# DistribPower_PWR.net
KiCad netlist of a schematic drawn in Altium Designer
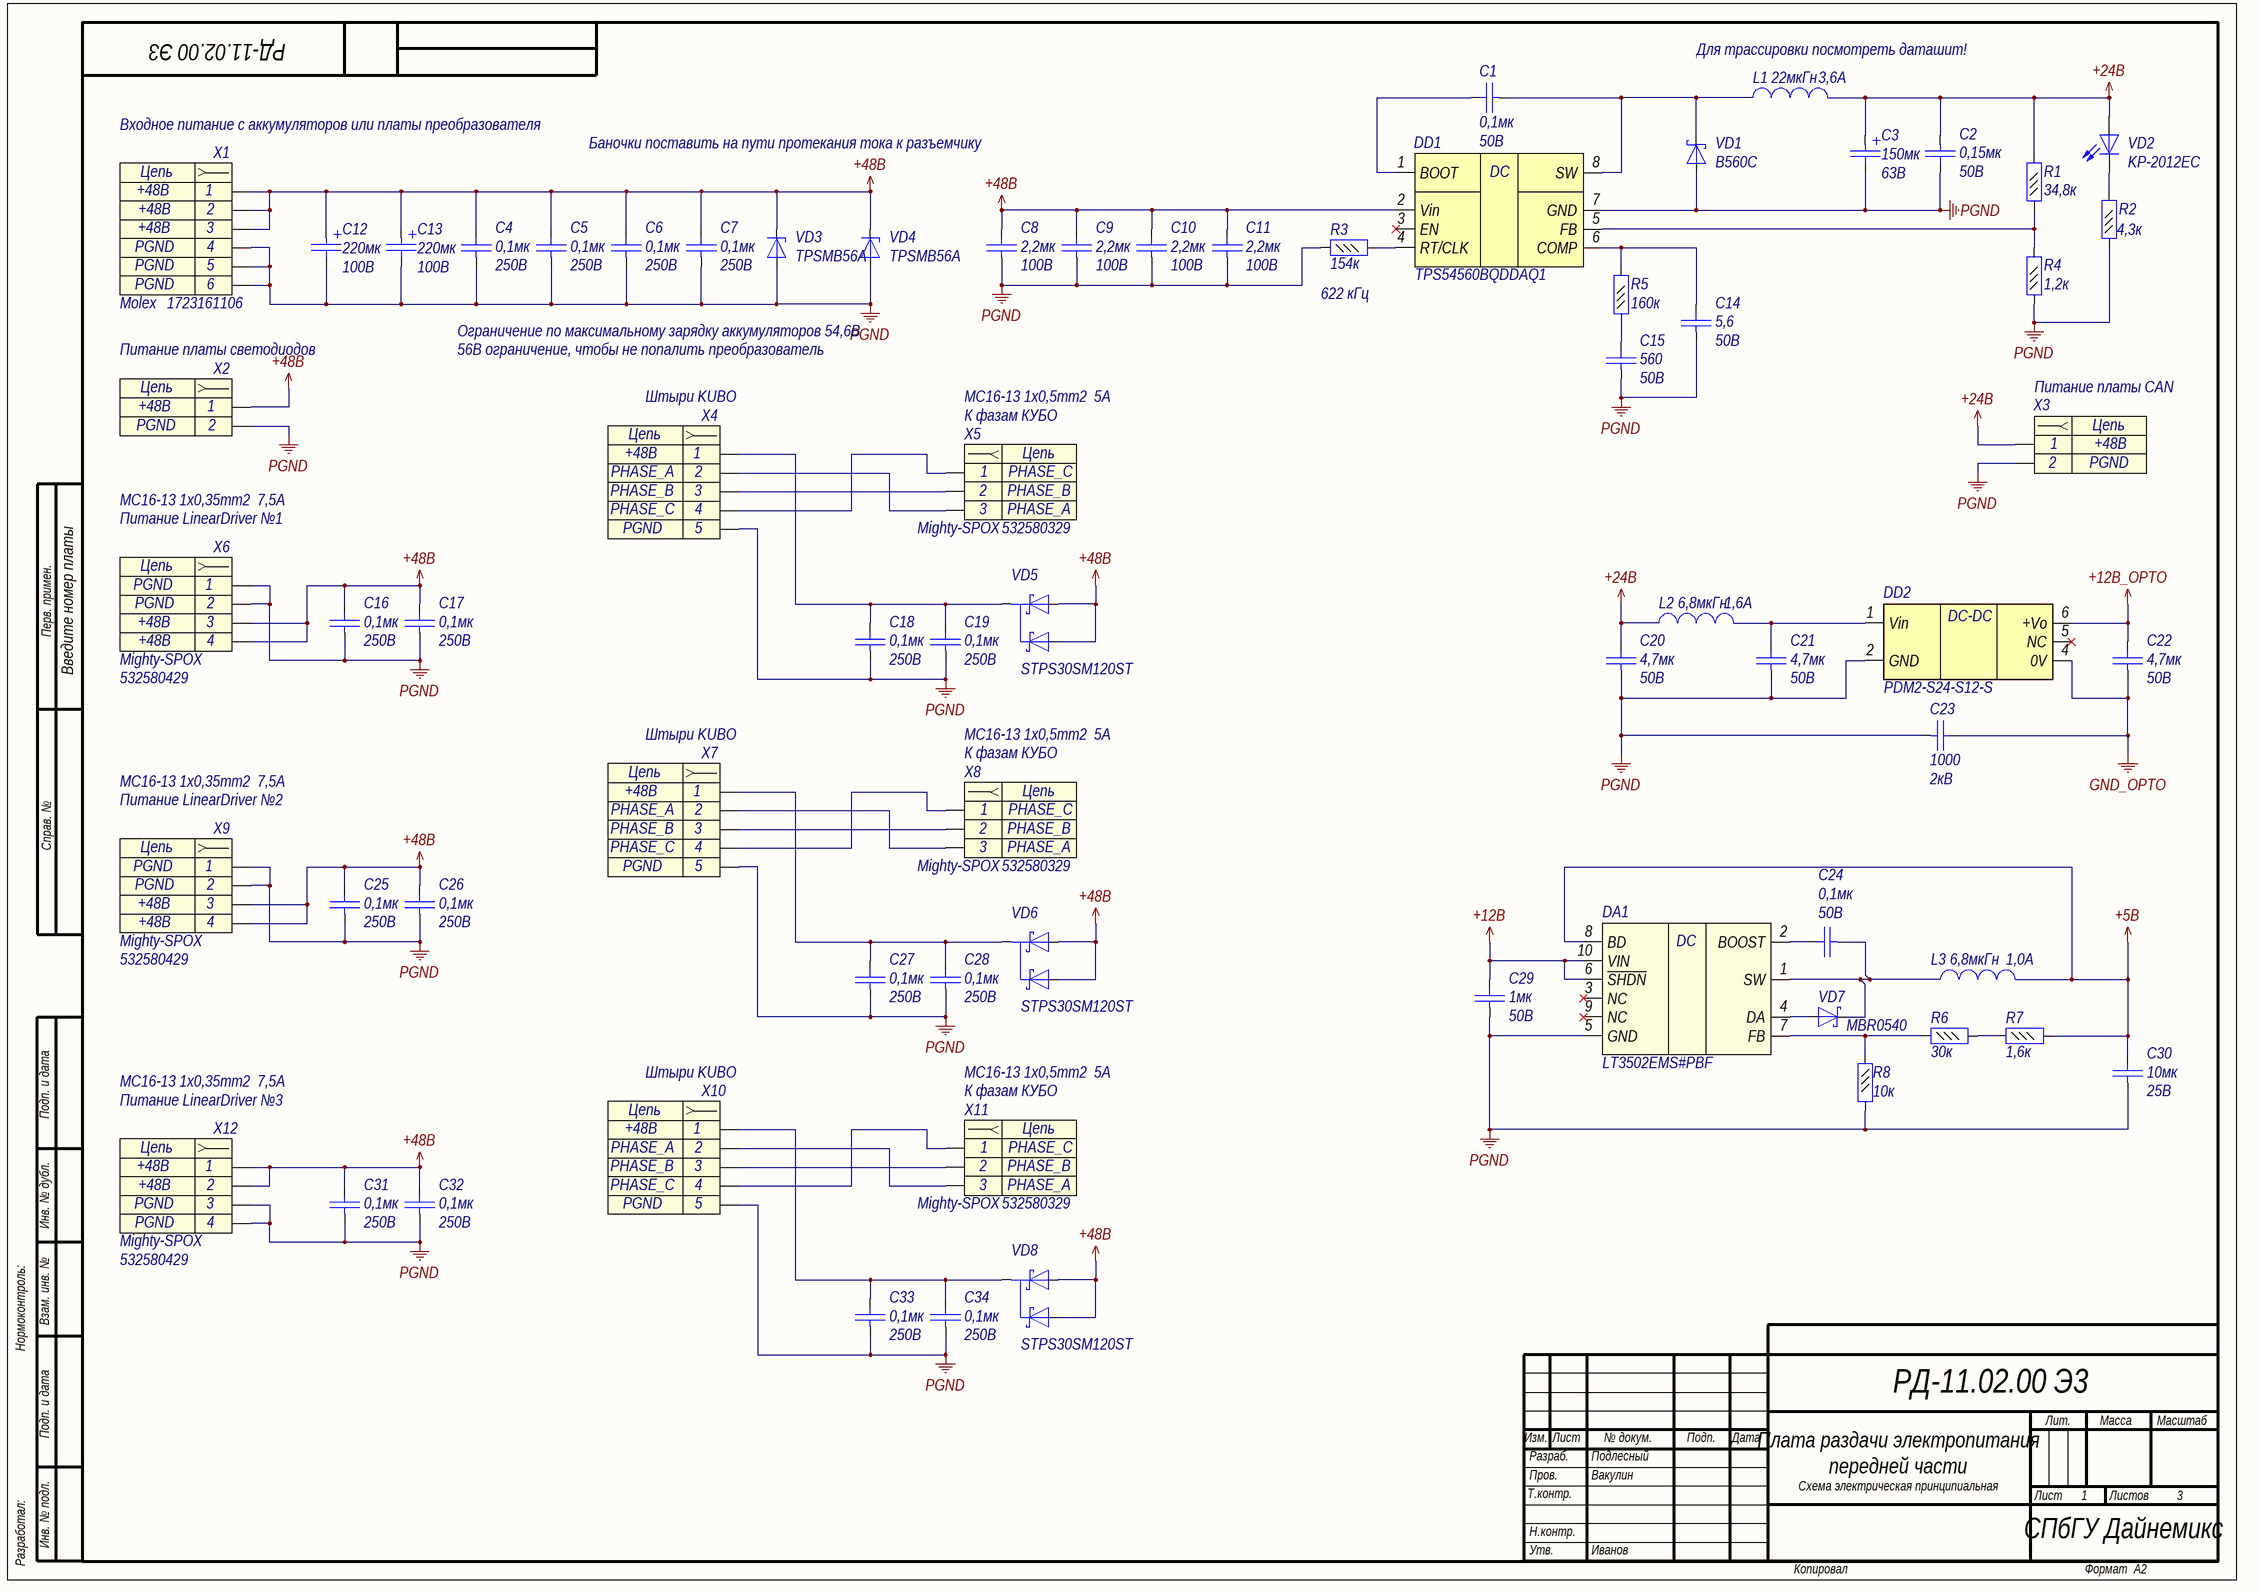
[diagram p0: DistribPower_PWR.SchDoc]

(export (version "E")
  (design (tool "Eeschema 10.0.6"))
  (components
    (comp (ref "C1")
      (value "0,1мк")
      (footprint "C0402")
      (description "Конденсатор")
      (fields (field (name "VOLTAGE") "50В") (field (name "PART NUMBER") "GRM155R71H104KE14D "))
      (libsource (lib "MOP44") (part "Capacitor"))
    )
    (comp (ref "C2")
      (value "0,15мк")
      (footprint "C1812")
      (description "Конденсатор")
      (fields (field (name "VOLTAGE") "50В") (field (name "PART NUMBER") "C4532C0G1H154J250KA "))
      (libsource (lib "MOP44") (part "Capacitor"))
    )
    (comp (ref "C3")
      (value "150мк")
      (footprint "Cap_SMD_radial_polar(10x16.5)")
      (description "Конденсатор полярный")
      (fields
        (field (name "VOLTAGE") "63B")
        (field (name "PART NUMBER") "EEH-ZS1J151P")
        (field (name "Comment") "Capacitor_pol")
      )
      (libsource (lib "MOP44") (part "Capacitor_pol"))
    )
    (comp (ref "C4")
      (value "0,1мк")
      (footprint "C1206")
      (description "Конденсатор")
      (fields
        (field (name "VOLTAGE") "250В")
        (field (name "PART NUMBER") "GRM31CR72E104K")
        (field (name "Comment") "Capacitor")
      )
      (libsource (lib "MOP44") (part "Capacitor"))
    )
    (comp (ref "C5")
      (value "0,1мк")
      (footprint "C1206")
      (description "Конденсатор")
      (fields
        (field (name "VOLTAGE") "250В")
        (field (name "PART NUMBER") "GRM31CR72E104K")
        (field (name "Comment") "Capacitor")
      )
      (libsource (lib "MOP44") (part "Capacitor"))
    )
    (comp (ref "C6")
      (value "0,1мк")
      (footprint "C1206")
      (description "Конденсатор")
      (fields
        (field (name "VOLTAGE") "250В")
        (field (name "PART NUMBER") "GRM31CR72E104K")
        (field (name "Comment") "Capacitor")
      )
      (libsource (lib "MOP44") (part "Capacitor"))
    )
    (comp (ref "C7")
      (value "0,1мк")
      (footprint "C1206")
      (description "Конденсатор")
      (fields
        (field (name "VOLTAGE") "250В")
        (field (name "PART NUMBER") "GRM31CR72E104K")
        (field (name "Comment") "Capacitor")
      )
      (libsource (lib "MOP44") (part "Capacitor"))
    )
    (comp (ref "C8")
      (value "2,2мк")
      (footprint "C1812")
      (description "Конденсатор")
      (fields (field (name "VOLTAGE") "100В") (field (name "PART NUMBER") "C4532X7R2A225M"))
      (libsource (lib "MOP44") (part "Capacitor"))
    )
    (comp (ref "C9")
      (value "2,2мк")
      (footprint "C1812")
      (description "Конденсатор")
      (fields (field (name "VOLTAGE") "100В") (field (name "PART NUMBER") "C4532X7R2A225M"))
      (libsource (lib "MOP44") (part "Capacitor"))
    )
    (comp (ref "C10")
      (value "2,2мк")
      (footprint "C1812")
      (description "Конденсатор")
      (fields (field (name "VOLTAGE") "100В") (field (name "PART NUMBER") "C4532X7R2A225M"))
      (libsource (lib "MOP44") (part "Capacitor"))
    )
    (comp (ref "C11")
      (value "2,2мк")
      (footprint "C1812")
      (description "Конденсатор")
      (fields (field (name "VOLTAGE") "100В") (field (name "PART NUMBER") "C4532X7R2A225M"))
      (libsource (lib "MOP44") (part "Capacitor"))
    )
    (comp (ref "C12")
      (value "220мк")
      (footprint "K50-35(12.5X25)_V")
      (description "Конденсатор полярный")
      (fields
        (field (name "VOLTAGE") "100B")
        (field (name "PART NUMBER") "B41851A9227M000")
        (field (name "Comment") "Capacitor_pol")
      )
      (libsource (lib "MOP44") (part "Capacitor_pol"))
    )
    (comp (ref "C13")
      (value "220мк")
      (footprint "K50-35(12.5X25)_V")
      (description "Конденсатор полярный")
      (fields
        (field (name "VOLTAGE") "100B")
        (field (name "PART NUMBER") "B41851A9227M000")
        (field (name "Comment") "Capacitor_pol")
      )
      (libsource (lib "MOP44") (part "Capacitor_pol"))
    )
    (comp (ref "C14")
      (value "5,6")
      (footprint "C0402")
      (description "Конденсатор")
      (fields (field (name "VOLTAGE") "50B") (field (name "PART NUMBER") "GRM1555C1H5R6C"))
      (libsource (lib "MOP44") (part "Capacitor"))
    )
    (comp (ref "C15")
      (value "560")
      (footprint "C0402")
      (description "Конденсатор")
      (fields (field (name "VOLTAGE") "50B") (field (name "PART NUMBER") "GRM1555C1H561J"))
      (libsource (lib "MOP44") (part "Capacitor"))
    )
    (comp (ref "C16")
      (value "0,1мк")
      (footprint "C1206")
      (description "Конденсатор")
      (fields
        (field (name "VOLTAGE") "250В")
        (field (name "PART NUMBER") "GRM31CR72E104K")
        (field (name "Comment") "Capacitor")
      )
      (libsource (lib "MOP44") (part "Capacitor"))
    )
    (comp (ref "C17")
      (value "0,1мк")
      (footprint "C1206")
      (description "Конденсатор")
      (fields
        (field (name "VOLTAGE") "250В")
        (field (name "PART NUMBER") "GRM31CR72E104K")
        (field (name "Comment") "Capacitor")
      )
      (libsource (lib "MOP44") (part "Capacitor"))
    )
    (comp (ref "C18")
      (value "0,1мк")
      (footprint "C1206")
      (description "Конденсатор")
      (fields
        (field (name "VOLTAGE") "250В")
        (field (name "PART NUMBER") "GRM31CR72E104K")
        (field (name "Comment") "Capacitor")
      )
      (libsource (lib "MOP44") (part "Capacitor"))
    )
    (comp (ref "C19")
      (value "0,1мк")
      (footprint "C1206")
      (description "Конденсатор")
      (fields
        (field (name "VOLTAGE") "250В")
        (field (name "PART NUMBER") "GRM31CR72E104K")
        (field (name "Comment") "Capacitor")
      )
      (libsource (lib "MOP44") (part "Capacitor"))
    )
    (comp (ref "C20")
      (value "4,7мк")
      (footprint "C1206")
      (description "Конденсатор")
      (fields (field (name "VOLTAGE") "50В") (field (name "PART NUMBER") "GRM31CR71H475KA12L"))
      (libsource (lib "MOP44") (part "Capacitor"))
    )
    (comp (ref "C21")
      (value "4,7мк")
      (footprint "C1206")
      (description "Конденсатор")
      (fields (field (name "VOLTAGE") "50В") (field (name "PART NUMBER") "GRM31CR71H475KA12L"))
      (libsource (lib "MOP44") (part "Capacitor"))
    )
    (comp (ref "C22")
      (value "4,7мк")
      (footprint "C1206")
      (description "Конденсатор")
      (fields (field (name "VOLTAGE") "50В") (field (name "PART NUMBER") "GRM31CR71H475KA12L"))
      (libsource (lib "MOP44") (part "Capacitor"))
    )
    (comp (ref "C23")
      (value "1000")
      (footprint "C1808")
      (description "Конденсатор")
      (fields (field (name "VOLTAGE") "2кB") (field (name "PART NUMBER") "GR442QR73D102KW01L"))
      (libsource (lib "MOP44") (part "Capacitor"))
    )
    (comp (ref "C24")
      (value "0,1мк")
      (footprint "C0402")
      (description "Конденсатор")
      (fields
        (field (name "VOLTAGE") "50В")
        (field (name "PART NUMBER") "GRM155R71H104KE14D ")
        (field (name "Comment") "Capacitor")
      )
      (libsource (lib "MOP44") (part "Capacitor"))
    )
    (comp (ref "C25")
      (value "0,1мк")
      (footprint "C1206")
      (description "Конденсатор")
      (fields
        (field (name "VOLTAGE") "250В")
        (field (name "PART NUMBER") "GRM31CR72E104K")
        (field (name "Comment") "Capacitor")
      )
      (libsource (lib "MOP44") (part "Capacitor"))
    )
    (comp (ref "C26")
      (value "0,1мк")
      (footprint "C1206")
      (description "Конденсатор")
      (fields
        (field (name "VOLTAGE") "250В")
        (field (name "PART NUMBER") "GRM31CR72E104K")
        (field (name "Comment") "Capacitor")
      )
      (libsource (lib "MOP44") (part "Capacitor"))
    )
    (comp (ref "C27")
      (value "0,1мк")
      (footprint "C1206")
      (description "Конденсатор")
      (fields
        (field (name "VOLTAGE") "250В")
        (field (name "PART NUMBER") "GRM31CR72E104K")
        (field (name "Comment") "Capacitor")
      )
      (libsource (lib "MOP44") (part "Capacitor"))
    )
    (comp (ref "C28")
      (value "0,1мк")
      (footprint "C1206")
      (description "Конденсатор")
      (fields
        (field (name "VOLTAGE") "250В")
        (field (name "PART NUMBER") "GRM31CR72E104K")
        (field (name "Comment") "Capacitor")
      )
      (libsource (lib "MOP44") (part "Capacitor"))
    )
    (comp (ref "C29")
      (value "1мк")
      (footprint "C0805")
      (description "Конденсатор")
      (fields
        (field (name "VOLTAGE") "50B")
        (field (name "PART NUMBER") "GRM21BR71H105K")
        (field (name "Comment") "Capacitor")
      )
      (libsource (lib "MOP44") (part "Capacitor"))
    )
    (comp (ref "C30")
      (value "10мк")
      (footprint "C1206")
      (description "Конденсатор")
      (fields
        (field (name "VOLTAGE") "25В")
        (field (name "PART NUMBER") "GRM31CR71E106KA12L*")
        (field (name "Comment") "Capacitor")
      )
      (libsource (lib "MOP44") (part "Capacitor"))
    )
    (comp (ref "C31")
      (value "0,1мк")
      (footprint "C1206")
      (description "Конденсатор")
      (fields
        (field (name "VOLTAGE") "250В")
        (field (name "PART NUMBER") "GRM31CR72E104K")
        (field (name "Comment") "Capacitor")
      )
      (libsource (lib "MOP44") (part "Capacitor"))
    )
    (comp (ref "C32")
      (value "0,1мк")
      (footprint "C1206")
      (description "Конденсатор")
      (fields
        (field (name "VOLTAGE") "250В")
        (field (name "PART NUMBER") "GRM31CR72E104K")
        (field (name "Comment") "Capacitor")
      )
      (libsource (lib "MOP44") (part "Capacitor"))
    )
    (comp (ref "C33")
      (value "0,1мк")
      (footprint "C1206")
      (description "Конденсатор")
      (fields
        (field (name "VOLTAGE") "250В")
        (field (name "PART NUMBER") "GRM31CR72E104K")
        (field (name "Comment") "Capacitor")
      )
      (libsource (lib "MOP44") (part "Capacitor"))
    )
    (comp (ref "C34")
      (value "0,1мк")
      (footprint "C1206")
      (description "Конденсатор")
      (fields
        (field (name "VOLTAGE") "250В")
        (field (name "PART NUMBER") "GRM31CR72E104K")
        (field (name "Comment") "Capacitor")
      )
      (libsource (lib "MOP44") (part "Capacitor"))
    )
    (comp (ref "DA1")
      (value "LT3502_MS")
      (footprint "MSOP10")
      (description "1.1MHz/2.2MHz, 500mA  Step-Down Regulators")
      (fields (field (name "PART NUMBER") "LT3502EMS#PBF") (field (name "MANUFACTURER") "Linear Technology"))
      (libsource (lib "MOP44") (part "LT3502_MS"))
    )
    (comp (ref "DD1")
      (value "TPS54560")
      (footprint "SO Powerpad8")
      (description "5-A, Wide Input Range, Step-Down Converter")
      (fields
        (field (name "PART NUMBER") "TPS54560BQDDAQ1")
        (field (name "MANUFACTURER") "Texas Instruments")
      )
      (libsource (lib "MOP44") (part "TPS54560"))
    )
    (comp (ref "DD2")
      (value "PDM2-Sxx-Sxx-S")
      (footprint "SIP6")
      (description "DC/DC преобразователь изолированный")
      (fields (field (name "PART NUMBER") "PDM2-S24-S12-S") (field (name "MANUFACTURER") "CUI INC"))
      (libsource (lib "MOP44") (part "PDM2-Sxx-Sxx-S"))
    )
    (comp (ref "L1")
      (value "22мкГн")
      (footprint "IND_12.5x12.5")
      (description "EMI Suppression Filter")
      (fields
        (field (name "RATED CURRENT") "3,6A")
        (field (name "PART NUMBER") "B82477G4223M000")
        (field (name "Comment") "Inductor")
      )
      (libsource (lib "MOP44") (part "Inductor"))
    )
    (comp (ref "L2")
      (value "6,8мкГн")
      (footprint "SDR0604")
      (description "EMI Suppression Filter")
      (fields
        (field (name "RATED CURRENT") "1,6A")
        (field (name "PART NUMBER") "SDR0604-6R8ML")
        (field (name "Comment") "Inductor")
      )
      (libsource (lib "MOP44") (part "Inductor"))
    )
    (comp (ref "L3")
      (value "6,8мкГн")
      (footprint "SDR0302")
      (description "EMI Suppression Filter")
      (fields
        (field (name "RATED CURRENT") "1,0A")
        (field (name "PART NUMBER") "SDR0302-6R8ML")
        (field (name "Comment") "Inductor")
      )
      (libsource (lib "MOP44") (part "Inductor"))
    )
    (comp (ref "R1")
      (value "34,8к")
      (footprint "R0402")
      (description "Резистор")
      (fields (field (name "PART NUMBER") "RC0402FR-0734K8L") (field (name "POWER") "0,062Вт"))
      (libsource (lib "MOP44") (part "Resistor_0,062Вт"))
    )
    (comp (ref "R2")
      (value "4,3к")
      (footprint "R0402")
      (description "Резистор")
      (fields (field (name "PART NUMBER") "RC0402FR-074K3") (field (name "POWER") "0,062Вт"))
      (libsource (lib "MOP44") (part "Resistor_0,062Вт"))
    )
    (comp (ref "R3")
      (value "154к")
      (footprint "R0402")
      (description "Резистор")
      (fields (field (name "PART NUMBER") "RC0402FR-07154KL") (field (name "POWER") "0,062Вт"))
      (libsource (lib "") (part "Resistor_0,062Вт_1"))
    )
    (comp (ref "R4")
      (value "1,2к")
      (footprint "R0402")
      (description "Резистор")
      (fields (field (name "PART NUMBER") "RC0402FR-071K2") (field (name "POWER") "0,062Вт"))
      (libsource (lib "MOP44") (part "Resistor_0,062Вт"))
    )
    (comp (ref "R5")
      (value "160к")
      (footprint "R0402")
      (description "Резистор")
      (fields (field (name "PART NUMBER") "RC0402FR-07160KL") (field (name "POWER") "0,062Вт"))
      (libsource (lib "MOP44") (part "Resistor_0,062Вт"))
    )
    (comp (ref "R6")
      (value "30к")
      (footprint "R0402")
      (description "Резистор")
      (fields (field (name "PART NUMBER") "RC0402FR-0730KL") (field (name "POWER") "0,062Вт"))
      (libsource (lib "") (part "Resistor_0,062Вт_1"))
    )
    (comp (ref "R7")
      (value "1,6к")
      (footprint "R0402")
      (description "Резистор")
      (fields (field (name "PART NUMBER") "RC0402FR-071K6") (field (name "POWER") "0,062Вт"))
      (libsource (lib "") (part "Resistor_0,062Вт_1"))
    )
    (comp (ref "R8")
      (value "10к")
      (footprint "R0402")
      (description "Резистор")
      (fields (field (name "PART NUMBER") "RC0402FR-0710KL") (field (name "POWER") "0,062Вт"))
      (libsource (lib "") (part "Resistor_0,062Вт_2"))
    )
    (comp (ref "VD1")
      (value "DiodeSchottky")
      (footprint "SMC")
      (description "Диод Шоттки")
      (fields (field (name "PART NUMBER") "B560C"))
      (libsource (lib "MOP44") (part "DiodeSchottky"))
    )
    (comp (ref "VD2")
      (value "LED")
      (footprint "L_0805")
      (description "Светодиод")
      (fields (field (name "PART NUMBER") "KP-2012EC"))
      (libsource (lib "MOP44") (part "LED"))
    )
    (comp (ref "VD3")
      (value "DiodeZener")
      (footprint "SMB")
      (description "Cтабилитрон (лавинный выпрямительный диод) односторонний")
      (fields (field (name "PART NUMBER") "TPSMB56A"))
      (libsource (lib "MOP44") (part "DiodeZener"))
    )
    (comp (ref "VD4")
      (value "DiodeZener")
      (footprint "SMB")
      (description "Cтабилитрон (лавинный выпрямительный диод) односторонний")
      (fields (field (name "PART NUMBER") "TPSMB56A"))
      (libsource (lib "MOP44") (part "DiodeZener"))
    )
    (comp (ref "VD5")
      (value "DiodeSchottkyDual")
      (footprint "TO-220AB-3_RAD")
      (description "Диод Шоттки")
      (fields (field (name "PART NUMBER") "STPS30SM120ST"))
      (libsource (lib "MOP44") (part "DiodeSchottkyDual"))
    )
    (comp (ref "VD6")
      (value "DiodeSchottkyDual")
      (footprint "TO-220AB-3_RAD")
      (description "Диод Шоттки")
      (fields (field (name "PART NUMBER") "STPS30SM120ST"))
      (libsource (lib "MOP44") (part "DiodeSchottkyDual"))
    )
    (comp (ref "VD7")
      (value "DiodeSchottky")
      (footprint "SOD-123")
      (description "Диод Шоттки")
      (fields (field (name "PART NUMBER") "MBR0540"))
      (libsource (lib "MOP44") (part "DiodeSchottky"))
    )
    (comp (ref "VD8")
      (value "DiodeSchottkyDual")
      (footprint "TO-220AB-3_RAD")
      (description "Диод Шоттки")
      (fields (field (name "PART NUMBER") "STPS30SM120ST"))
      (libsource (lib "MOP44") (part "DiodeSchottkyDual"))
    )
    (comp (ref "X1")
      (value "Header_6_sct")
      (footprint "MOLEX_1723161106")
      (description "Разъем - 6 конт. розетка")
      (fields (field (name "PART NUMBER") "1723161106") (field (name "MANUFACTURE") "Molex"))
      (libsource (lib "MOP44") (part "Header_6_sct"))
    )
    (comp (ref "X2")
      (value "Питание платы светодиодов")
      (footprint "MOLEX_532580229")
      (description "Разъем - 2 конт. розетка")
      (fields (field (name "PART NUMBER") "532580229"))
      (libsource (lib "") (part "Header_2_sct_1"))
    )
    (comp (ref "X3")
      (value "Питание платы CAN")
      (footprint "MOLEX_532580229")
      (description "Разъем - 2 конт. розетка")
      (fields (field (name "PART NUMBER") "532580229"))
      (libsource (lib "MOP44") (part "Header_2_sct"))
    )
    (comp (ref "X4")
      (value "Штыри KUBO")
      (footprint "KUBO")
      (description "Разъем - 5 конт. розетка")
      (libsource (lib "MOP44") (part "Header_5_sct"))
    )
    (comp (ref "X5")
      (value "К фазам КУБО")
      (footprint "MOLEX_532580329")
      (description "Разъем - 3 конт. розетка")
      (fields (field (name "PART NAME") "Mighty-SPOX") (field (name "PART NUMBER") "532580329"))
      (libsource (lib "MOP44") (part "Header_3_sct"))
    )
    (comp (ref "X6")
      (value "Питание LinearDriver №1")
      (footprint "MOLEX_532580429")
      (description "Разъем - 4 конт. розетка")
      (fields (field (name "PART NAME") "Mighty-SPOX") (field (name "PART NUMBER") "532580429"))
      (libsource (lib "MOP44") (part "Header_4_sct"))
    )
    (comp (ref "X7")
      (value "Штыри KUBO")
      (footprint "KUBO")
      (description "Разъем - 5 конт. розетка")
      (libsource (lib "MOP44") (part "Header_5_sct"))
    )
    (comp (ref "X8")
      (value "К фазам КУБО")
      (footprint "MOLEX_532580329")
      (description "Разъем - 3 конт. розетка")
      (fields (field (name "PART NAME") "Mighty-SPOX") (field (name "PART NUMBER") "532580329"))
      (libsource (lib "MOP44") (part "Header_3_sct"))
    )
    (comp (ref "X9")
      (value "Питание LinearDriver №2")
      (footprint "MOLEX_532580429")
      (description "Разъем - 4 конт. розетка")
      (fields (field (name "PART NAME") "Mighty-SPOX") (field (name "PART NUMBER") "532580429"))
      (libsource (lib "MOP44") (part "Header_4_sct"))
    )
    (comp (ref "X10")
      (value "Штыри KUBO")
      (footprint "KUBO")
      (description "Разъем - 5 конт. розетка")
      (libsource (lib "MOP44") (part "Header_5_sct"))
    )
    (comp (ref "X11")
      (value "К фазам КУБО")
      (footprint "MOLEX_532580329")
      (description "Разъем - 3 конт. розетка")
      (fields (field (name "PART NAME") "Mighty-SPOX") (field (name "PART NUMBER") "532580329"))
      (libsource (lib "MOP44") (part "Header_3_sct"))
    )
    (comp (ref "X12")
      (value "Питание LinearDriver №3")
      (footprint "MOLEX_532580429")
      (description "Разъем - 4 конт. розетка")
      (fields (field (name "PART NAME") "Mighty-SPOX") (field (name "PART NUMBER") "532580429"))
      (libsource (lib "MOP44") (part "Header_4_sct"))
    )
  )
  (nets
    (net (code "1") (name "+5B") (class "Default")
      (node (ref "C30") (pin "2") (pinfunction "2_2") (pintype "passive"))
      (node (ref "DA1") (pin "8") (pinfunction "BD_8") (pintype "power_in"))
      (node (ref "L3") (pin "2") (pinfunction "2_2") (pintype "passive"))
      (node (ref "R7") (pin "2") (pinfunction "2_2") (pintype "passive"))
    )
    (net (code "2") (name "+12B") (class "Default")
      (node (ref "C29") (pin "2") (pinfunction "2_2") (pintype "passive"))
      (node (ref "DA1") (pin "10") (pinfunction "VIN_10") (pintype "power_in"))
      (node (ref "DA1") (pin "6") (pinfunction "~{SHDN}_6") (pintype "power_in"))
    )
    (net (code "3") (name "+12B_OPTO") (class "Default")
      (node (ref "C22") (pin "2") (pinfunction "2_2") (pintype "passive"))
      (node (ref "DD2") (pin "6") (pinfunction "+Vo_6") (pintype "passive"))
    )
    (net (code "4") (name "+24B") (class "Default")
      (node (ref "C2") (pin "1") (pinfunction "1_1") (pintype "passive"))
      (node (ref "C20") (pin "2") (pinfunction "2_2") (pintype "passive"))
      (node (ref "C3") (pin "1") (pinfunction "1_1") (pintype "passive"))
      (node (ref "L1") (pin "2") (pinfunction "2_2") (pintype "passive"))
      (node (ref "L2") (pin "1") (pinfunction "1_1") (pintype "passive"))
      (node (ref "R1") (pin "2") (pinfunction "2_2") (pintype "passive"))
      (node (ref "VD2") (pin "2") (pinfunction "A_2") (pintype "passive"))
      (node (ref "X3") (pin "1") (pinfunction "1_1") (pintype "passive"))
    )
    (net (code "5") (name "+48B") (class "Default")
      (node (ref "C10") (pin "2") (pinfunction "2_2") (pintype "passive"))
      (node (ref "C11") (pin "2") (pinfunction "2_2") (pintype "passive"))
      (node (ref "C12") (pin "1") (pinfunction "1_1") (pintype "passive"))
      (node (ref "C13") (pin "1") (pinfunction "1_1") (pintype "passive"))
      (node (ref "C16") (pin "2") (pinfunction "2_2") (pintype "passive"))
      (node (ref "C17") (pin "2") (pinfunction "2_2") (pintype "passive"))
      (node (ref "C25") (pin "2") (pinfunction "2_2") (pintype "passive"))
      (node (ref "C26") (pin "2") (pinfunction "2_2") (pintype "passive"))
      (node (ref "C31") (pin "2") (pinfunction "2_2") (pintype "passive"))
      (node (ref "C32") (pin "2") (pinfunction "2_2") (pintype "passive"))
      (node (ref "C4") (pin "2") (pinfunction "2_2") (pintype "passive"))
      (node (ref "C5") (pin "2") (pinfunction "2_2") (pintype "passive"))
      (node (ref "C6") (pin "2") (pinfunction "2_2") (pintype "passive"))
      (node (ref "C7") (pin "2") (pinfunction "2_2") (pintype "passive"))
      (node (ref "C8") (pin "2") (pinfunction "2_2") (pintype "passive"))
      (node (ref "C9") (pin "2") (pinfunction "2_2") (pintype "passive"))
      (node (ref "DD1") (pin "2") (pinfunction "Vin_2") (pintype "passive"))
      (node (ref "VD3") (pin "1") (pinfunction "K_1") (pintype "passive"))
      (node (ref "VD4") (pin "1") (pinfunction "K_1") (pintype "passive"))
      (node (ref "VD5") (pin "1") (pinfunction "A_1") (pintype "passive"))
      (node (ref "VD5") (pin "3") (pinfunction "A_3") (pintype "passive"))
      (node (ref "VD6") (pin "1") (pinfunction "A_1") (pintype "passive"))
      (node (ref "VD6") (pin "3") (pinfunction "A_3") (pintype "passive"))
      (node (ref "VD8") (pin "1") (pinfunction "A_1") (pintype "passive"))
      (node (ref "VD8") (pin "3") (pinfunction "A_3") (pintype "passive"))
      (node (ref "X1") (pin "1") (pinfunction "1_1") (pintype "passive"))
      (node (ref "X1") (pin "2") (pinfunction "2_2") (pintype "passive"))
      (node (ref "X1") (pin "3") (pinfunction "3_3") (pintype "passive"))
      (node (ref "X12") (pin "1") (pinfunction "1_1") (pintype "passive"))
      (node (ref "X12") (pin "2") (pinfunction "2_2") (pintype "passive"))
      (node (ref "X2") (pin "1") (pinfunction "1_1") (pintype "passive"))
      (node (ref "X6") (pin "3") (pinfunction "3_3") (pintype "passive"))
      (node (ref "X6") (pin "4") (pinfunction "4_4") (pintype "passive"))
      (node (ref "X9") (pin "3") (pinfunction "3_3") (pintype "passive"))
      (node (ref "X9") (pin "4") (pinfunction "4_4") (pintype "passive"))
    )
    (net (code "6") (name "GND_OPTO") (class "Default")
      (node (ref "C22") (pin "1") (pinfunction "1_1") (pintype "passive"))
      (node (ref "C23") (pin "2") (pinfunction "2_2") (pintype "passive"))
      (node (ref "DD2") (pin "4") (pinfunction "0V_4") (pintype "passive"))
    )
    (net (code "7") (name "Net-(C15-Pad2)") (class "Default")
      (node (ref "C15") (pin "2") (pinfunction "2_2") (pintype "passive"))
      (node (ref "R5") (pin "1") (pinfunction "1_1") (pintype "passive"))
    )
    (net (code "8") (name "Net-(DA1-BOOST)") (class "Default")
      (node (ref "C24") (pin "2") (pinfunction "2_2") (pintype "passive"))
      (node (ref "DA1") (pin "2") (pinfunction "BOOST_2") (pintype "power_in"))
    )
    (net (code "9") (name "Net-(DA1-DA)") (class "Default")
      (node (ref "DA1") (pin "4") (pinfunction "DA_4") (pintype "power_in"))
      (node (ref "VD7") (pin "2") (pinfunction "A_2") (pintype "passive"))
    )
    (net (code "10") (name "Net-(DA1-FB)") (class "Default")
      (node (ref "DA1") (pin "7") (pinfunction "FB_7") (pintype "power_in"))
      (node (ref "R6") (pin "1") (pinfunction "1_1") (pintype "passive"))
      (node (ref "R8") (pin "1") (pinfunction "1_1") (pintype "passive"))
    )
    (net (code "11") (name "Net-(DA1-SW)") (class "Default")
      (node (ref "C24") (pin "1") (pinfunction "1_1") (pintype "passive"))
      (node (ref "DA1") (pin "1") (pinfunction "SW_1") (pintype "power_in"))
      (node (ref "L3") (pin "1") (pinfunction "1_1") (pintype "passive"))
      (node (ref "VD7") (pin "1") (pinfunction "K_1") (pintype "passive"))
    )
    (net (code "12") (name "Net-(DD1-BOOT)") (class "Default")
      (node (ref "C1") (pin "2") (pinfunction "2_2") (pintype "passive"))
      (node (ref "DD1") (pin "1") (pinfunction "BOOT_1") (pintype "passive"))
    )
    (net (code "13") (name "Net-(DD1-COMP)") (class "Default")
      (node (ref "C14") (pin "2") (pinfunction "2_2") (pintype "passive"))
      (node (ref "DD1") (pin "6") (pinfunction "COMP_6") (pintype "passive"))
      (node (ref "R5") (pin "2") (pinfunction "2_2") (pintype "passive"))
    )
    (net (code "14") (name "Net-(DD1-FB)") (class "Default")
      (node (ref "DD1") (pin "5") (pinfunction "FB_5") (pintype "passive"))
      (node (ref "R1") (pin "1") (pinfunction "1_1") (pintype "passive"))
      (node (ref "R4") (pin "2") (pinfunction "2_2") (pintype "passive"))
    )
    (net (code "15") (name "Net-(DD1-RT{slash}CLK)") (class "Default")
      (node (ref "DD1") (pin "4") (pinfunction "RT/CLK_4") (pintype "passive"))
      (node (ref "R3") (pin "2") (pinfunction "2_2") (pintype "passive"))
    )
    (net (code "16") (name "Net-(DD1-SW)") (class "Default")
      (node (ref "C1") (pin "1") (pinfunction "1_1") (pintype "passive"))
      (node (ref "DD1") (pin "8") (pinfunction "SW_8") (pintype "passive"))
      (node (ref "L1") (pin "1") (pinfunction "1_1") (pintype "passive"))
      (node (ref "VD1") (pin "1") (pinfunction "K_1") (pintype "passive"))
    )
    (net (code "17") (name "Net-(DD2-Vin)") (class "Default")
      (node (ref "C21") (pin "2") (pinfunction "2_2") (pintype "passive"))
      (node (ref "DD2") (pin "1") (pinfunction "Vin_1") (pintype "passive"))
      (node (ref "L2") (pin "2") (pinfunction "2_2") (pintype "passive"))
    )
    (net (code "18") (name "Net-(R6-Pad2)") (class "Default")
      (node (ref "R6") (pin "2") (pinfunction "2_2") (pintype "passive"))
      (node (ref "R7") (pin "1") (pinfunction "1_1") (pintype "passive"))
    )
    (net (code "19") (name "Net-(VD2-K)") (class "Default")
      (node (ref "R2") (pin "2") (pinfunction "2_2") (pintype "passive"))
      (node (ref "VD2") (pin "1") (pinfunction "K_1") (pintype "passive"))
    )
    (net (code "20") (name "Net-(VD5-K)") (class "Default")
      (node (ref "C18") (pin "2") (pinfunction "2_2") (pintype "passive"))
      (node (ref "C19") (pin "2") (pinfunction "2_2") (pintype "passive"))
      (node (ref "VD5") (pin "2") (pinfunction "K_2") (pintype "passive"))
      (node (ref "X4") (pin "1") (pinfunction "1_1") (pintype "passive"))
    )
    (net (code "21") (name "Net-(VD6-K)") (class "Default")
      (node (ref "C27") (pin "2") (pinfunction "2_2") (pintype "passive"))
      (node (ref "C28") (pin "2") (pinfunction "2_2") (pintype "passive"))
      (node (ref "VD6") (pin "2") (pinfunction "K_2") (pintype "passive"))
      (node (ref "X7") (pin "1") (pinfunction "1_1") (pintype "passive"))
    )
    (net (code "22") (name "Net-(VD8-K)") (class "Default")
      (node (ref "C33") (pin "2") (pinfunction "2_2") (pintype "passive"))
      (node (ref "C34") (pin "2") (pinfunction "2_2") (pintype "passive"))
      (node (ref "VD8") (pin "2") (pinfunction "K_2") (pintype "passive"))
      (node (ref "X10") (pin "1") (pinfunction "1_1") (pintype "passive"))
    )
    (net (code "23") (name "Net-(X4-Pad2)") (class "Default")
      (node (ref "X4") (pin "2") (pinfunction "2_2") (pintype "passive"))
      (node (ref "X5") (pin "3") (pinfunction "3_3") (pintype "passive"))
    )
    (net (code "24") (name "Net-(X4-Pad3)") (class "Default")
      (node (ref "X4") (pin "3") (pinfunction "3_3") (pintype "passive"))
      (node (ref "X5") (pin "2") (pinfunction "2_2") (pintype "passive"))
    )
    (net (code "25") (name "Net-(X4-Pad4)") (class "Default")
      (node (ref "X4") (pin "4") (pinfunction "4_4") (pintype "passive"))
      (node (ref "X5") (pin "1") (pinfunction "1_1") (pintype "passive"))
    )
    (net (code "26") (name "Net-(X7-Pad2)") (class "Default")
      (node (ref "X7") (pin "2") (pinfunction "2_2") (pintype "passive"))
      (node (ref "X8") (pin "3") (pinfunction "3_3") (pintype "passive"))
    )
    (net (code "27") (name "Net-(X7-Pad3)") (class "Default")
      (node (ref "X7") (pin "3") (pinfunction "3_3") (pintype "passive"))
      (node (ref "X8") (pin "2") (pinfunction "2_2") (pintype "passive"))
    )
    (net (code "28") (name "Net-(X7-Pad4)") (class "Default")
      (node (ref "X7") (pin "4") (pinfunction "4_4") (pintype "passive"))
      (node (ref "X8") (pin "1") (pinfunction "1_1") (pintype "passive"))
    )
    (net (code "29") (name "Net-(X10-Pad2)") (class "Default")
      (node (ref "X10") (pin "2") (pinfunction "2_2") (pintype "passive"))
      (node (ref "X11") (pin "3") (pinfunction "3_3") (pintype "passive"))
    )
    (net (code "30") (name "Net-(X10-Pad3)") (class "Default")
      (node (ref "X10") (pin "3") (pinfunction "3_3") (pintype "passive"))
      (node (ref "X11") (pin "2") (pinfunction "2_2") (pintype "passive"))
    )
    (net (code "31") (name "Net-(X10-Pad4)") (class "Default")
      (node (ref "X10") (pin "4") (pinfunction "4_4") (pintype "passive"))
      (node (ref "X11") (pin "1") (pinfunction "1_1") (pintype "passive"))
    )
    (net (code "32") (name "PGND") (class "Default")
      (node (ref "C10") (pin "1") (pinfunction "1_1") (pintype "passive"))
      (node (ref "C11") (pin "1") (pinfunction "1_1") (pintype "passive"))
      (node (ref "C12") (pin "2") (pinfunction "2_2") (pintype "passive"))
      (node (ref "C13") (pin "2") (pinfunction "2_2") (pintype "passive"))
      (node (ref "C14") (pin "1") (pinfunction "1_1") (pintype "passive"))
      (node (ref "C15") (pin "1") (pinfunction "1_1") (pintype "passive"))
      (node (ref "C16") (pin "1") (pinfunction "1_1") (pintype "passive"))
      (node (ref "C17") (pin "1") (pinfunction "1_1") (pintype "passive"))
      (node (ref "C18") (pin "1") (pinfunction "1_1") (pintype "passive"))
      (node (ref "C19") (pin "1") (pinfunction "1_1") (pintype "passive"))
      (node (ref "C2") (pin "2") (pinfunction "2_2") (pintype "passive"))
      (node (ref "C20") (pin "1") (pinfunction "1_1") (pintype "passive"))
      (node (ref "C21") (pin "1") (pinfunction "1_1") (pintype "passive"))
      (node (ref "C23") (pin "1") (pinfunction "1_1") (pintype "passive"))
      (node (ref "C25") (pin "1") (pinfunction "1_1") (pintype "passive"))
      (node (ref "C26") (pin "1") (pinfunction "1_1") (pintype "passive"))
      (node (ref "C27") (pin "1") (pinfunction "1_1") (pintype "passive"))
      (node (ref "C28") (pin "1") (pinfunction "1_1") (pintype "passive"))
      (node (ref "C29") (pin "1") (pinfunction "1_1") (pintype "passive"))
      (node (ref "C3") (pin "2") (pinfunction "2_2") (pintype "passive"))
      (node (ref "C30") (pin "1") (pinfunction "1_1") (pintype "passive"))
      (node (ref "C31") (pin "1") (pinfunction "1_1") (pintype "passive"))
      (node (ref "C32") (pin "1") (pinfunction "1_1") (pintype "passive"))
      (node (ref "C33") (pin "1") (pinfunction "1_1") (pintype "passive"))
      (node (ref "C34") (pin "1") (pinfunction "1_1") (pintype "passive"))
      (node (ref "C4") (pin "1") (pinfunction "1_1") (pintype "passive"))
      (node (ref "C5") (pin "1") (pinfunction "1_1") (pintype "passive"))
      (node (ref "C6") (pin "1") (pinfunction "1_1") (pintype "passive"))
      (node (ref "C7") (pin "1") (pinfunction "1_1") (pintype "passive"))
      (node (ref "C8") (pin "1") (pinfunction "1_1") (pintype "passive"))
      (node (ref "C9") (pin "1") (pinfunction "1_1") (pintype "passive"))
      (node (ref "DA1") (pin "5") (pinfunction "GND_5") (pintype "power_in"))
      (node (ref "DD1") (pin "7") (pinfunction "GND_7") (pintype "passive"))
      (node (ref "DD2") (pin "2") (pinfunction "GND_2") (pintype "passive"))
      (node (ref "R2") (pin "1") (pinfunction "1_1") (pintype "passive"))
      (node (ref "R3") (pin "1") (pinfunction "1_1") (pintype "passive"))
      (node (ref "R4") (pin "1") (pinfunction "1_1") (pintype "passive"))
      (node (ref "R8") (pin "2") (pinfunction "2_2") (pintype "passive"))
      (node (ref "VD1") (pin "2") (pinfunction "A_2") (pintype "passive"))
      (node (ref "VD3") (pin "2") (pinfunction "A_2") (pintype "passive"))
      (node (ref "VD4") (pin "2") (pinfunction "A_2") (pintype "passive"))
      (node (ref "X1") (pin "4") (pinfunction "4_4") (pintype "passive"))
      (node (ref "X1") (pin "5") (pinfunction "5_5") (pintype "passive"))
      (node (ref "X1") (pin "6") (pinfunction "6_6") (pintype "passive"))
      (node (ref "X10") (pin "5") (pinfunction "5_5") (pintype "passive"))
      (node (ref "X12") (pin "3") (pinfunction "3_3") (pintype "passive"))
      (node (ref "X12") (pin "4") (pinfunction "4_4") (pintype "passive"))
      (node (ref "X2") (pin "2") (pinfunction "2_2") (pintype "passive"))
      (node (ref "X3") (pin "2") (pinfunction "2_2") (pintype "passive"))
      (node (ref "X4") (pin "5") (pinfunction "5_5") (pintype "passive"))
      (node (ref "X6") (pin "1") (pinfunction "1_1") (pintype "passive"))
      (node (ref "X6") (pin "2") (pinfunction "2_2") (pintype "passive"))
      (node (ref "X7") (pin "5") (pinfunction "5_5") (pintype "passive"))
      (node (ref "X9") (pin "1") (pinfunction "1_1") (pintype "passive"))
      (node (ref "X9") (pin "2") (pinfunction "2_2") (pintype "passive"))
    )
    (net (code "33") (name "unconnected-(DA1-NC-Pad3)") (class "Default")
      (node (ref "DA1") (pin "3") (pinfunction "NC_3") (pintype "power_in+no_connect"))
    )
    (net (code "34") (name "unconnected-(DA1-NC-Pad9)") (class "Default")
      (node (ref "DA1") (pin "9") (pinfunction "NC_9") (pintype "power_in+no_connect"))
    )
    (net (code "35") (name "unconnected-(DD1-EN-Pad3)") (class "Default")
      (node (ref "DD1") (pin "3") (pinfunction "EN_3") (pintype "passive+no_connect"))
    )
    (net (code "36") (name "unconnected-(DD2-NC-Pad5)") (class "Default")
      (node (ref "DD2") (pin "5") (pinfunction "NC_5") (pintype "passive+no_connect"))
    )
  )
)
